# MCISO-S08-V00-HallDifferentials.net
KiCad netlist of a schematic drawn in Altium Designer
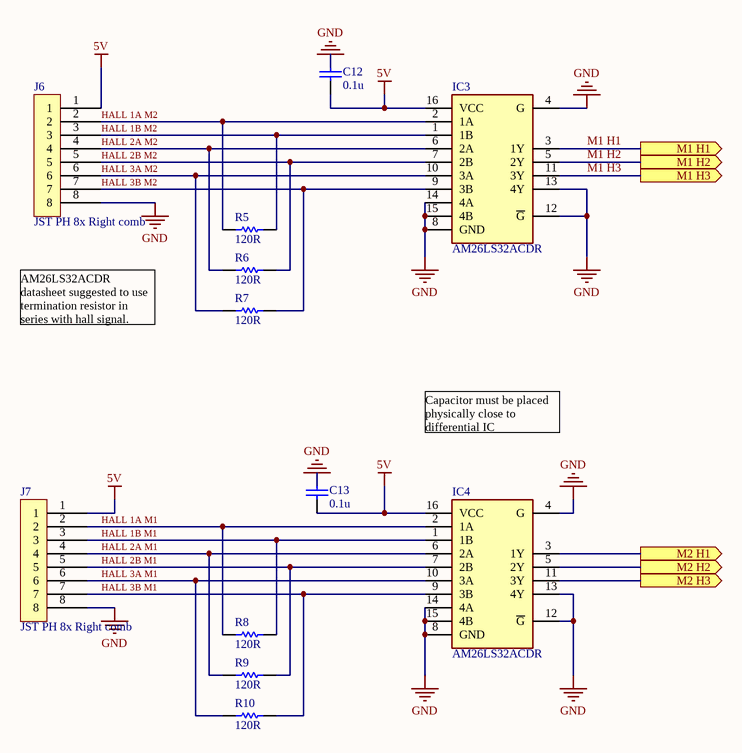
[diagram p0: MCISO-S08-V00-HallDifferentials.SchDoc]

(export (version "E")
  (design (tool "Eeschema 10.0.6"))
  (components
    (comp (ref "C12")
      (value "0.1u")
      (footprint "Cap_Ceramic_0603")
      (description "Capacitor, Ceramic, SMD, 4u7, 50V, 5%, X7R, 0603")
      (libsource (lib "QUTMS-MCISOLibrary") (part "4u7 50V 5% X7R 0603"))
    )
    (comp (ref "C13")
      (value "0.1u")
      (footprint "Cap_Ceramic_0603")
      (description "Capacitor, Ceramic, SMD, 4u7, 50V, 5%, X7R, 0603")
      (libsource (lib "QUTMS-MCISOLibrary") (part "4u7 50V 5% X7R 0603"))
    )
    (comp (ref "IC3")
      (value "AM26LS32ACDR")
      (footprint "SamacSys:SOIC127P600X175-16N")
      (description "Integrated Circuit")
      (fields (field (name "MOUSER PART NUMBER") "595-AM26LS32ACDR"))
      (libsource (lib "QUTMS-MCISOLibrary") (part "AM26LS32ACDR"))
    )
    (comp (ref "IC4")
      (value "AM26LS32ACDR")
      (footprint "SamacSys:SOIC127P600X175-16N")
      (description "Integrated Circuit")
      (fields (field (name "MOUSER PART NUMBER") "595-AM26LS32ACDR"))
      (libsource (lib "QUTMS-MCISOLibrary") (part "AM26LS32ACDR"))
    )
    (comp (ref "J6")
      (value "JST PH 8x Right comb")
      (footprint "JST PH 8x RIGHT SMD")
      (libsource (lib "QUTMS-MCISOLibrary") (part "JST PH 8x Right comb"))
    )
    (comp (ref "J7")
      (value "JST PH 8x Right comb")
      (footprint "JST PH 8x RIGHT SMD")
      (libsource (lib "QUTMS-MCISOLibrary") (part "JST PH 8x Right comb"))
    )
    (comp (ref "R5")
      (value "120R")
      (footprint "Res_ThinFilm_1210")
      (description "Resistor, SMD, 120R, 0.25W, 1%, 1210")
      (libsource (lib "QUTMS-MCISOLibrary") (part "120R 1% 1210"))
    )
    (comp (ref "R6")
      (value "120R")
      (footprint "Res_ThinFilm_1210")
      (description "Resistor, SMD, 120R, 0.25W, 1%, 1210")
      (libsource (lib "QUTMS-MCISOLibrary") (part "120R 1% 1210"))
    )
    (comp (ref "R7")
      (value "120R")
      (footprint "Res_ThinFilm_1210")
      (description "Resistor, SMD, 120R, 0.25W, 1%, 1210")
      (libsource (lib "QUTMS-MCISOLibrary") (part "120R 1% 1210"))
    )
    (comp (ref "R8")
      (value "120R")
      (footprint "Res_ThinFilm_1210")
      (description "Resistor, SMD, 120R, 0.25W, 1%, 1210")
      (libsource (lib "QUTMS-MCISOLibrary") (part "120R 1% 1210"))
    )
    (comp (ref "R9")
      (value "120R")
      (footprint "Res_ThinFilm_1210")
      (description "Resistor, SMD, 120R, 0.25W, 1%, 1210")
      (libsource (lib "QUTMS-MCISOLibrary") (part "120R 1% 1210"))
    )
    (comp (ref "R10")
      (value "120R")
      (footprint "Res_ThinFilm_1210")
      (description "Resistor, SMD, 120R, 0.25W, 1%, 1210")
      (libsource (lib "QUTMS-MCISOLibrary") (part "120R 1% 1210"))
    )
  )
  (nets
    (net (code "1") (name "/HALL 1A M1") (class "Default")
      (node (ref "IC4") (pin "2") (pinfunction "1A_2") (pintype "passive"))
      (node (ref "J7") (pin "2") (pinfunction "2_2") (pintype "passive"))
      (node (ref "R8") (pin "1") (pinfunction "1_1") (pintype "passive"))
    )
    (net (code "2") (name "/HALL 1A M2") (class "Default")
      (node (ref "IC3") (pin "2") (pinfunction "1A_2") (pintype "passive"))
      (node (ref "J6") (pin "2") (pinfunction "2_2") (pintype "passive"))
      (node (ref "R5") (pin "1") (pinfunction "1_1") (pintype "passive"))
    )
    (net (code "3") (name "/HALL 1B M1") (class "Default")
      (node (ref "IC4") (pin "1") (pinfunction "1B_1") (pintype "passive"))
      (node (ref "J7") (pin "3") (pinfunction "3_3") (pintype "passive"))
      (node (ref "R8") (pin "2") (pinfunction "2_2") (pintype "passive"))
    )
    (net (code "4") (name "/HALL 1B M2") (class "Default")
      (node (ref "IC3") (pin "1") (pinfunction "1B_1") (pintype "passive"))
      (node (ref "J6") (pin "3") (pinfunction "3_3") (pintype "passive"))
      (node (ref "R5") (pin "2") (pinfunction "2_2") (pintype "passive"))
    )
    (net (code "5") (name "/HALL 2A M1") (class "Default")
      (node (ref "IC4") (pin "6") (pinfunction "2A_6") (pintype "passive"))
      (node (ref "J7") (pin "4") (pinfunction "4_4") (pintype "passive"))
      (node (ref "R9") (pin "1") (pinfunction "1_1") (pintype "passive"))
    )
    (net (code "6") (name "/HALL 2A M2") (class "Default")
      (node (ref "IC3") (pin "6") (pinfunction "2A_6") (pintype "passive"))
      (node (ref "J6") (pin "4") (pinfunction "4_4") (pintype "passive"))
      (node (ref "R6") (pin "1") (pinfunction "1_1") (pintype "passive"))
    )
    (net (code "7") (name "/HALL 2B M1") (class "Default")
      (node (ref "IC4") (pin "7") (pinfunction "2B_7") (pintype "passive"))
      (node (ref "J7") (pin "5") (pinfunction "5_5") (pintype "passive"))
      (node (ref "R9") (pin "2") (pinfunction "2_2") (pintype "passive"))
    )
    (net (code "8") (name "/HALL 2B M2") (class "Default")
      (node (ref "IC3") (pin "7") (pinfunction "2B_7") (pintype "passive"))
      (node (ref "J6") (pin "5") (pinfunction "5_5") (pintype "passive"))
      (node (ref "R6") (pin "2") (pinfunction "2_2") (pintype "passive"))
    )
    (net (code "9") (name "/HALL 3A M1") (class "Default")
      (node (ref "IC4") (pin "10") (pinfunction "3A_10") (pintype "passive"))
      (node (ref "J7") (pin "6") (pinfunction "6_6") (pintype "passive"))
      (node (ref "R10") (pin "1") (pinfunction "1_1") (pintype "passive"))
    )
    (net (code "10") (name "/HALL 3A M2") (class "Default")
      (node (ref "IC3") (pin "10") (pinfunction "3A_10") (pintype "passive"))
      (node (ref "J6") (pin "6") (pinfunction "6_6") (pintype "passive"))
      (node (ref "R7") (pin "1") (pinfunction "1_1") (pintype "passive"))
    )
    (net (code "11") (name "/HALL 3B M1") (class "Default")
      (node (ref "IC4") (pin "9") (pinfunction "3B_9") (pintype "passive"))
      (node (ref "J7") (pin "7") (pinfunction "7_7") (pintype "passive"))
      (node (ref "R10") (pin "2") (pinfunction "2_2") (pintype "passive"))
    )
    (net (code "12") (name "/HALL 3B M2") (class "Default")
      (node (ref "IC3") (pin "9") (pinfunction "3B_9") (pintype "passive"))
      (node (ref "J6") (pin "7") (pinfunction "7_7") (pintype "passive"))
      (node (ref "R7") (pin "2") (pinfunction "2_2") (pintype "passive"))
    )
    (net (code "13") (name "/M1 H1") (class "Default")
      (node (ref "IC3") (pin "3") (pinfunction "1Y_3") (pintype "passive"))
    )
    (net (code "14") (name "/M1 H2") (class "Default")
      (node (ref "IC3") (pin "5") (pinfunction "2Y_5") (pintype "passive"))
    )
    (net (code "15") (name "/M1 H3") (class "Default")
      (node (ref "IC3") (pin "11") (pinfunction "3Y_11") (pintype "passive"))
    )
    (net (code "16") (name "/M2 H1") (class "Default")
      (node (ref "IC4") (pin "3") (pinfunction "1Y_3") (pintype "passive"))
    )
    (net (code "17") (name "/M2 H2") (class "Default")
      (node (ref "IC4") (pin "5") (pinfunction "2Y_5") (pintype "passive"))
    )
    (net (code "18") (name "/M2 H3") (class "Default")
      (node (ref "IC4") (pin "11") (pinfunction "3Y_11") (pintype "passive"))
    )
    (net (code "19") (name "5V") (class "Default")
      (node (ref "C12") (pin "2") (pinfunction "2_2") (pintype "passive"))
      (node (ref "C13") (pin "2") (pinfunction "2_2") (pintype "passive"))
      (node (ref "IC3") (pin "16") (pinfunction "VCC_16") (pintype "passive"))
      (node (ref "IC4") (pin "16") (pinfunction "VCC_16") (pintype "passive"))
      (node (ref "J6") (pin "1") (pinfunction "1_1") (pintype "passive"))
      (node (ref "J7") (pin "1") (pinfunction "1_1") (pintype "passive"))
    )
    (net (code "20") (name "GND") (class "Default")
      (node (ref "C12") (pin "1") (pinfunction "1_1") (pintype "passive"))
      (node (ref "C13") (pin "1") (pinfunction "1_1") (pintype "passive"))
      (node (ref "IC3") (pin "12") (pinfunction "~{G}_12") (pintype "passive"))
      (node (ref "IC3") (pin "13") (pinfunction "4Y_13") (pintype "passive"))
      (node (ref "IC3") (pin "14") (pinfunction "4A_14") (pintype "passive"))
      (node (ref "IC3") (pin "15") (pinfunction "4B_15") (pintype "passive"))
      (node (ref "IC3") (pin "4") (pinfunction "G_4") (pintype "passive"))
      (node (ref "IC3") (pin "8") (pinfunction "GND_8") (pintype "passive"))
      (node (ref "IC4") (pin "12") (pinfunction "~{G}_12") (pintype "passive"))
      (node (ref "IC4") (pin "13") (pinfunction "4Y_13") (pintype "passive"))
      (node (ref "IC4") (pin "14") (pinfunction "4A_14") (pintype "passive"))
      (node (ref "IC4") (pin "15") (pinfunction "4B_15") (pintype "passive"))
      (node (ref "IC4") (pin "4") (pinfunction "G_4") (pintype "passive"))
      (node (ref "IC4") (pin "8") (pinfunction "GND_8") (pintype "passive"))
      (node (ref "J6") (pin "8") (pinfunction "8_8") (pintype "passive"))
      (node (ref "J7") (pin "8") (pinfunction "8_8") (pintype "passive"))
    )
  )
)
